# Tile-carrier.net
KiCad netlist of a schematic drawn in Altium Designer
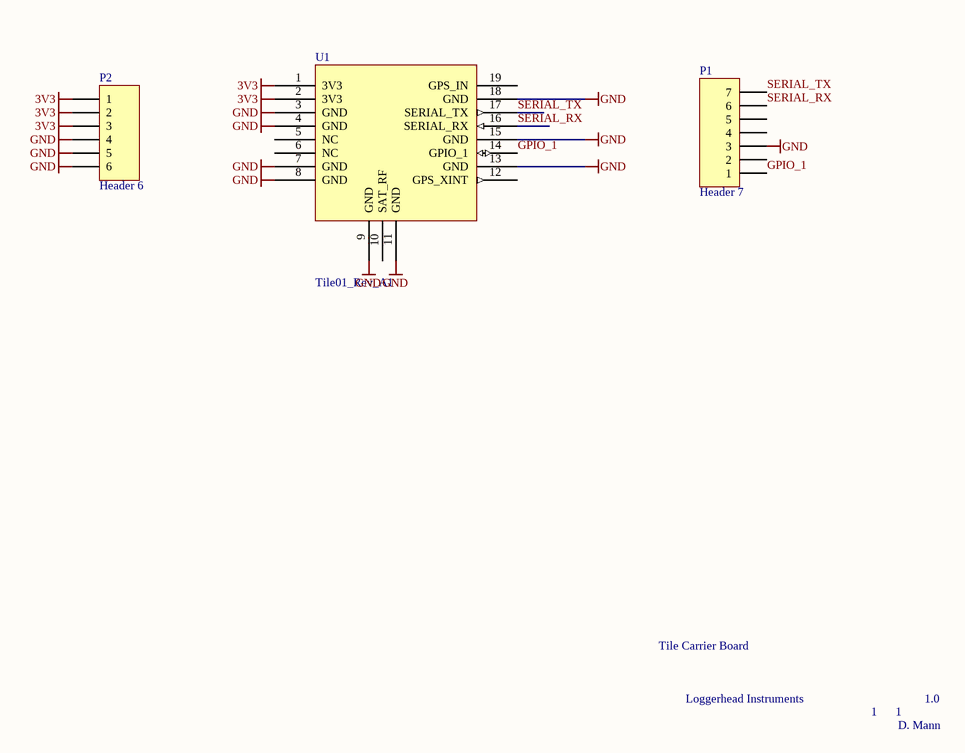
[diagram p0: Tile-carrier.SchDoc]

(export (version "E")
  (design (tool "Eeschema 10.0.6"))
  (components
    (comp (ref "P1")
      (value "Header 7")
      (footprint "HDR1X7")
      (description "Header, 7-Pin")
      (fields (field (name "PUBLISHER") "Altium Limited"))
      (libsource (lib "Miscellaneous Connectors") (part "Header 7"))
    )
    (comp (ref "P2")
      (value "Header 6")
      (footprint "HDR1X6")
      (description "Header, 6-Pin")
      (fields (field (name "PUBLISHER") "Altium Limited"))
      (libsource (lib "Miscellaneous Connectors") (part "Header 6"))
    )
    (comp (ref "U1")
      (value "~")
      (footprint "Tile01:Tile01 Rev A1")
      (description "SWARM: Tile01 Rev A1 VHF")
      (fields (field (name "VOLTAGE") "3V3") (field (name "MANUF1 P/N") "Tile01_Rev_A1"))
      (libsource (lib "Tile01") (part "Tile01 Rev A1"))
    )
  )
  (nets
    (net (code "1") (name "/GPIO_1") (class "Default")
      (node (ref "P1") (pin "1") (pinfunction "1_1") (pintype "passive"))
      (node (ref "U1") (pin "14") (pinfunction "GPIO_1_14") (pintype "bidirectional"))
    )
    (net (code "2") (name "/SERIAL_RX") (class "Default")
      (node (ref "P1") (pin "6") (pinfunction "6_6") (pintype "passive"))
      (node (ref "U1") (pin "16") (pinfunction "SERIAL_RX_16") (pintype "input"))
    )
    (net (code "3") (name "/SERIAL_TX") (class "Default")
      (node (ref "P1") (pin "7") (pinfunction "7_7") (pintype "passive"))
      (node (ref "U1") (pin "17") (pinfunction "SERIAL_TX_17") (pintype "output"))
    )
    (net (code "4") (name "3V3") (class "Default")
      (node (ref "P2") (pin "1") (pinfunction "1_1") (pintype "passive"))
      (node (ref "P2") (pin "2") (pinfunction "2_2") (pintype "passive"))
      (node (ref "P2") (pin "3") (pinfunction "3_3") (pintype "passive"))
      (node (ref "U1") (pin "1") (pinfunction "3V3_1") (pintype "power_in"))
      (node (ref "U1") (pin "2") (pinfunction "3V3_2") (pintype "power_in"))
    )
    (net (code "5") (name "GND") (class "Default")
      (node (ref "P1") (pin "3") (pinfunction "3_3") (pintype "passive"))
      (node (ref "P2") (pin "4") (pinfunction "4_4") (pintype "passive"))
      (node (ref "P2") (pin "5") (pinfunction "5_5") (pintype "passive"))
      (node (ref "P2") (pin "6") (pinfunction "6_6") (pintype "passive"))
      (node (ref "U1") (pin "11") (pinfunction "GND_11") (pintype "power_in"))
      (node (ref "U1") (pin "13") (pinfunction "GND_13") (pintype "power_in"))
      (node (ref "U1") (pin "15") (pinfunction "GND_15") (pintype "power_in"))
      (node (ref "U1") (pin "18") (pinfunction "GND_18") (pintype "power_in"))
      (node (ref "U1") (pin "3") (pinfunction "GND_3") (pintype "power_in"))
      (node (ref "U1") (pin "4") (pinfunction "GND_4") (pintype "passive"))
      (node (ref "U1") (pin "7") (pinfunction "GND_7") (pintype "power_in"))
      (node (ref "U1") (pin "8") (pinfunction "GND_8") (pintype "power_in"))
      (node (ref "U1") (pin "9") (pinfunction "GND_9") (pintype "power_in"))
    )
    (net (code "6") (name "unconnected-(P1-Pad2)") (class "Default")
      (node (ref "P1") (pin "2") (pinfunction "2_2") (pintype "passive"))
    )
    (net (code "7") (name "unconnected-(P1-Pad4)") (class "Default")
      (node (ref "P1") (pin "4") (pinfunction "4_4") (pintype "passive"))
    )
    (net (code "8") (name "unconnected-(P1-Pad5)") (class "Default")
      (node (ref "P1") (pin "5") (pinfunction "5_5") (pintype "passive"))
    )
    (net (code "9") (name "unconnected-(U1-GPS_IN-Pad19)") (class "Default")
      (node (ref "U1") (pin "19") (pinfunction "GPS_IN_19") (pintype "passive"))
    )
    (net (code "10") (name "unconnected-(U1-GPS_XINT-Pad12)") (class "Default")
      (node (ref "U1") (pin "12") (pinfunction "GPS_XINT_12") (pintype "output"))
    )
    (net (code "11") (name "unconnected-(U1-NC-Pad5)") (class "Default")
      (node (ref "U1") (pin "5") (pinfunction "NC_5") (pintype "power_in"))
    )
    (net (code "12") (name "unconnected-(U1-NC-Pad6)") (class "Default")
      (node (ref "U1") (pin "6") (pinfunction "NC_6") (pintype "power_in"))
    )
    (net (code "13") (name "unconnected-(U1-SAT_RF-Pad10)") (class "Default")
      (node (ref "U1") (pin "10") (pinfunction "SAT_RF_10") (pintype "passive"))
    )
  )
)
